# External_Camera_HAT_Regulators.net
KiCad netlist of a schematic drawn in Altium Designer
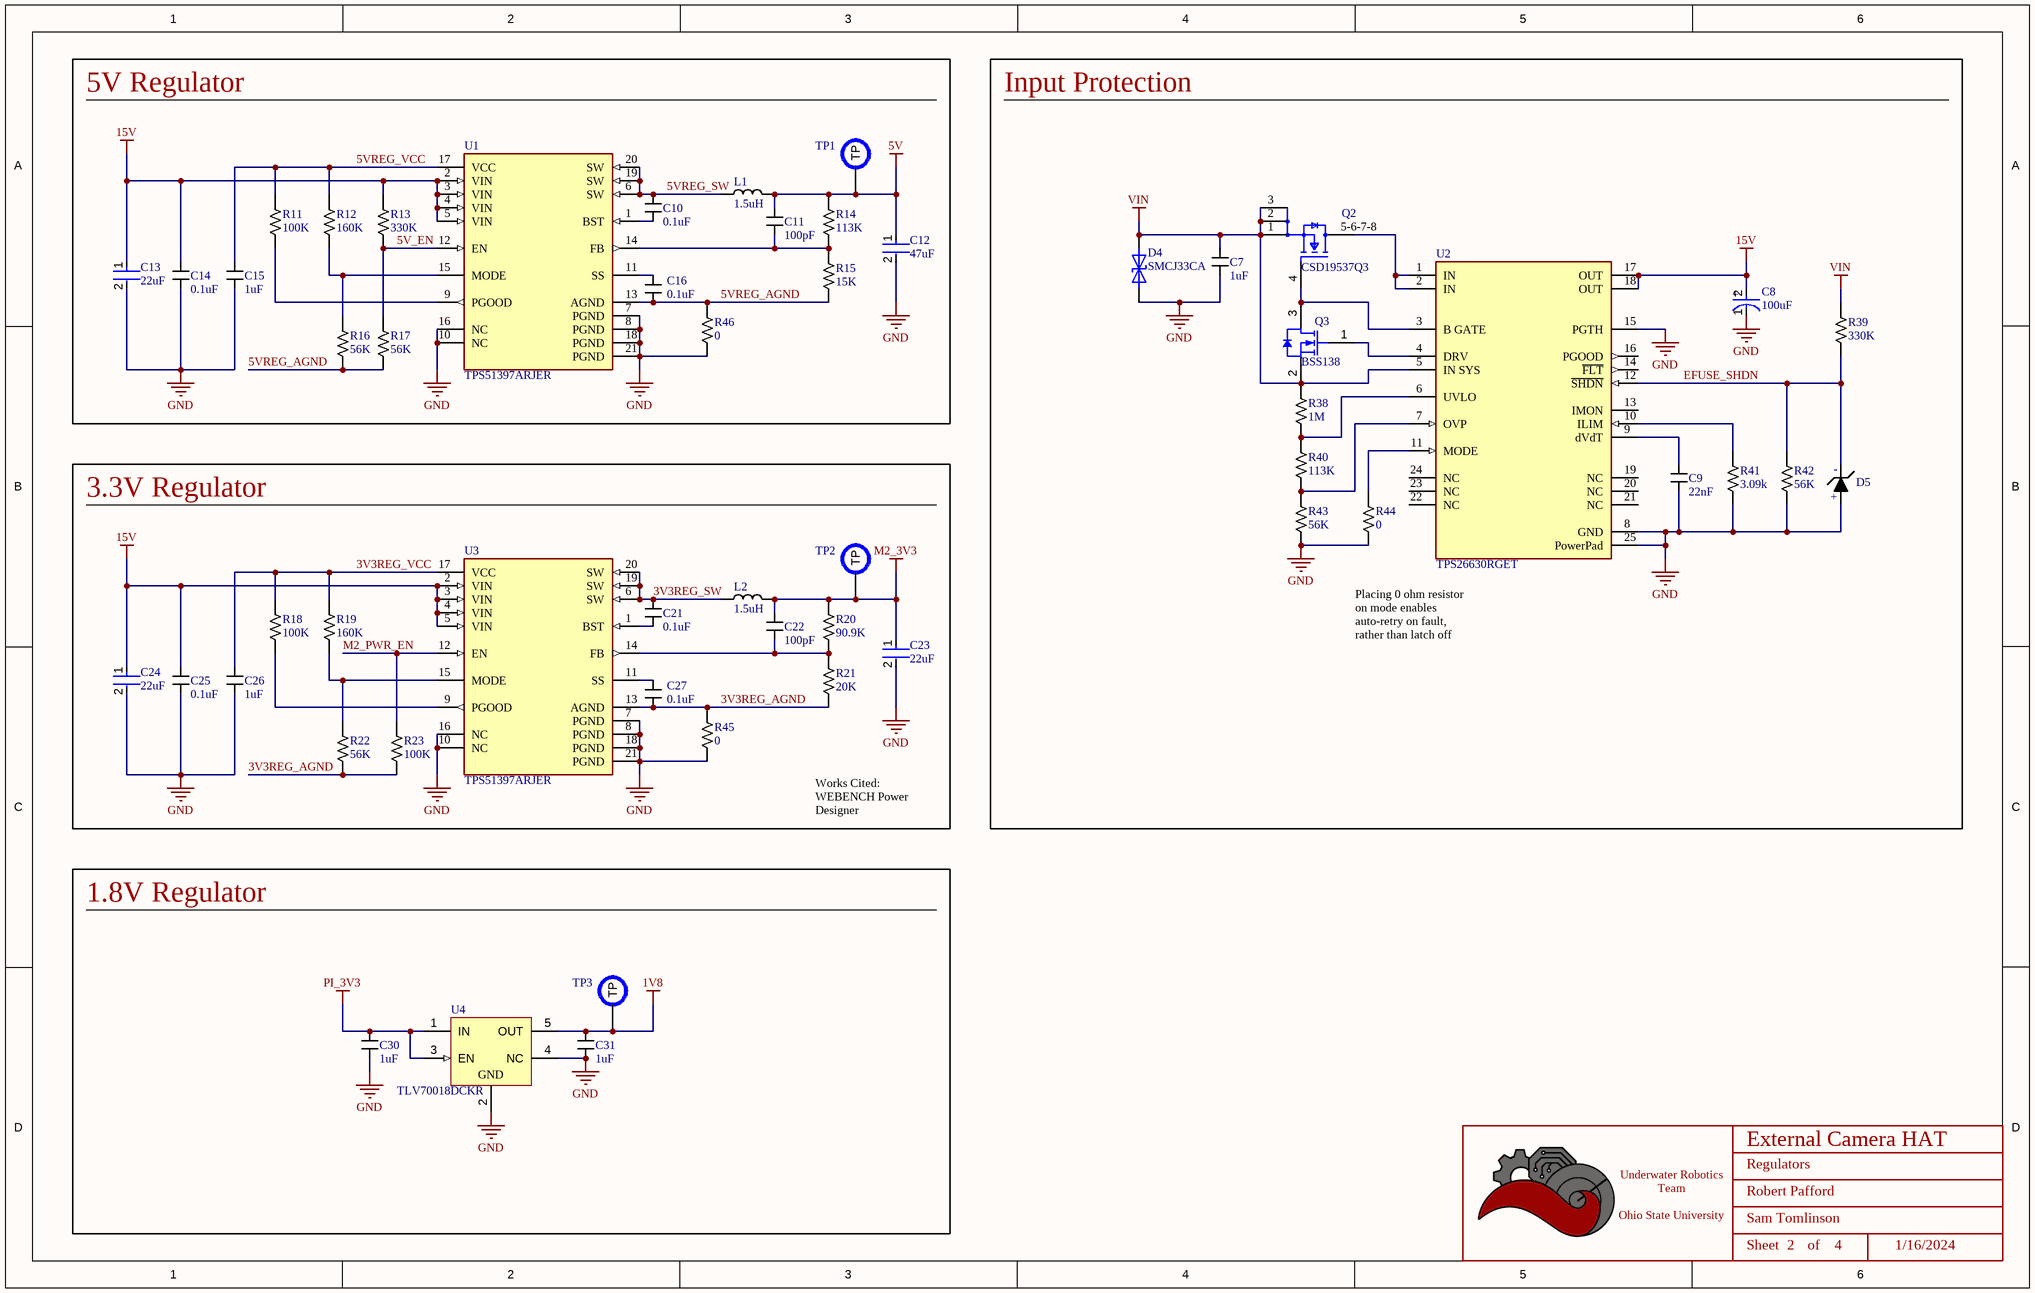
[diagram p0: External_Camera_HAT_Regulators.SchDoc]

(export (version "E")
  (design (tool "Eeschema 10.0.6"))
  (components
    (comp (ref "C7")
      (value "1uF")
      (footprint "CAPACITOR_0603")
      (description "Cap 1uF 25V +/-10%\r\nCeramic 0603")
      (fields
        (field (name "TOLERANCE") "+/- 10%")
        (field (name "VOLTAGE") "16V")
        (field (name "MADE BY") "Flip B")
      )
      (libsource (lib "Capacitors") (part "CAPACITOR_1uF_0603_25V"))
    )
    (comp (ref "C8")
      (value "100uF")
      (footprint "FP-UWT1H101MNL1GS-MFG")
      (description "CAP ALUM 100UF 20% 50V SMD")
      (fields (field (name "TOLERANCE") "20%") (field (name "VOLTAGE") "50V"))
      (libsource (lib "Altium Content Vault") (part "203bc49f2ac43e59fd269a8c329ed05"))
    )
    (comp (ref "C9")
      (value "22nF")
      (footprint "CAPACITOR_0402")
      (description "Cap 22nF 25V +/-10%\r\nCeramic 0402")
      (fields
        (field (name "TOLERANCE") "+/- 10%")
        (field (name "VOLTAGE") "25V")
        (field (name "MADE BY") "Robert Pafford")
      )
      (libsource (lib "Capacitors") (part "CAPACITOR_0.022uF_0402"))
    )
    (comp (ref "C10")
      (value "0.1uF")
      (footprint "CAPACITOR_0402")
      (description "Cap 100nF 25V +/-10%\r\nCeramic 0402")
      (fields
        (field (name "TOLERANCE") "+/- 10%")
        (field (name "VOLTAGE") "25V")
        (field (name "MADE BY") "Robert Pafford")
      )
      (libsource (lib "Capacitors") (part "CAPACITOR_0.1uF_0402"))
    )
    (comp (ref "C11")
      (value "100pF")
      (footprint "CAPACITOR_0402")
      (description "Cap 100pF 25V +/-10%\r\nCeramic 0402")
      (fields
        (field (name "TOLERANCE") "+/- 10%")
        (field (name "VOLTAGE") "25V")
        (field (name "MADE BY") "Robert Pafford")
      )
      (libsource (lib "Capacitors") (part "CAPACITOR_0.0001uF_0402"))
    )
    (comp (ref "C12")
      (value "GRM31CR61A476KE15L")
      (footprint "FP-GRM31C-0_2-e0_3_0_8-MFG")
      (description "Chip Multilayer Ceramic Capacitors for General Purpose, 1206, 47uF, X5R, 15%, 10%, 10V")
      (fields
        (field (name "TOLERANCE") "10%")
        (field (name "VOLTAGE") "10V")
        (field (name "CAPACITANCE") "47uF")
      )
      (libsource (lib "Altium Content Vault") (part "02cd4be3c70576c341d710602a673aa"))
    )
    (comp (ref "C13")
      (value "C2012X5R1V226M125AC")
      (footprint "FP-C2012-125-0_2-MFG")
      (description "Multilayer Ceramic Capacitors 22μF ±20% 35V X5R SMD 0805")
      (fields (field (name "TOLERANCE") "20%") (field (name "CAPACITANCE") "22uF"))
      (libsource (lib "Altium Content Vault") (part "b4654b650e69147ec39a6b967a45e02"))
    )
    (comp (ref "C14")
      (value "0.1uF")
      (footprint "CAPACITOR_0402")
      (description "Cap 100nF 25V +/-10%\r\nCeramic 0402")
      (fields
        (field (name "TOLERANCE") "+/- 10%")
        (field (name "VOLTAGE") "25V")
        (field (name "MADE BY") "Robert Pafford")
      )
      (libsource (lib "Capacitors") (part "CAPACITOR_0.1uF_0402"))
    )
    (comp (ref "C15")
      (value "1uF")
      (footprint "CAPACITOR_0402")
      (description "Cap 1uF 16V +/-10%\r\nCeramic 0402")
      (fields
        (field (name "TOLERANCE") "+/- 10%")
        (field (name "VOLTAGE") "16V")
        (field (name "MADE BY") "Robert Pafford")
      )
      (libsource (lib "Capacitors") (part "CAPACITOR_1uF_0402"))
    )
    (comp (ref "C16")
      (value "0.1uF")
      (footprint "CAPACITOR_0402")
      (description "Cap 100nF 25V +/-10%\r\nCeramic 0402")
      (fields
        (field (name "TOLERANCE") "+/- 10%")
        (field (name "VOLTAGE") "25V")
        (field (name "MADE BY") "Robert Pafford")
      )
      (libsource (lib "Capacitors") (part "CAPACITOR_0.1uF_0402"))
    )
    (comp (ref "C21")
      (value "0.1uF")
      (footprint "CAPACITOR_0402")
      (description "Cap 100nF 25V +/-10%\r\nCeramic 0402")
      (fields
        (field (name "TOLERANCE") "+/- 10%")
        (field (name "VOLTAGE") "25V")
        (field (name "MADE BY") "Robert Pafford")
      )
      (libsource (lib "Capacitors") (part "CAPACITOR_0.1uF_0402"))
    )
    (comp (ref "C22")
      (value "100pF")
      (footprint "CAPACITOR_0402")
      (description "Cap 100pF 25V +/-10%\r\nCeramic 0402")
      (fields
        (field (name "TOLERANCE") "+/- 10%")
        (field (name "VOLTAGE") "25V")
        (field (name "MADE BY") "Robert Pafford")
      )
      (libsource (lib "Capacitors") (part "CAPACITOR_0.0001uF_0402"))
    )
    (comp (ref "C23")
      (value "C2012X5R1V226M125AC")
      (footprint "FP-C2012-125-0_2-MFG")
      (description "Multilayer Ceramic Capacitors 22μF ±20% 35V X5R SMD 0805")
      (fields (field (name "TOLERANCE") "20%") (field (name "CAPACITANCE") "22uF"))
      (libsource (lib "Altium Content Vault") (part "b4654b650e69147ec39a6b967a45e02"))
    )
    (comp (ref "C24")
      (value "C2012X5R1V226M125AC")
      (footprint "FP-C2012-125-0_2-MFG")
      (description "Multilayer Ceramic Capacitors 22μF ±20% 35V X5R SMD 0805")
      (fields (field (name "TOLERANCE") "20%") (field (name "CAPACITANCE") "22uF"))
      (libsource (lib "Altium Content Vault") (part "b4654b650e69147ec39a6b967a45e02"))
    )
    (comp (ref "C25")
      (value "0.1uF")
      (footprint "CAPACITOR_0402")
      (description "Cap 100nF 25V +/-10%\r\nCeramic 0402")
      (fields
        (field (name "TOLERANCE") "+/- 10%")
        (field (name "VOLTAGE") "25V")
        (field (name "MADE BY") "Robert Pafford")
      )
      (libsource (lib "Capacitors") (part "CAPACITOR_0.1uF_0402"))
    )
    (comp (ref "C26")
      (value "1uF")
      (footprint "CAPACITOR_0402")
      (description "Cap 1uF 16V +/-10%\r\nCeramic 0402")
      (fields
        (field (name "TOLERANCE") "+/- 10%")
        (field (name "VOLTAGE") "16V")
        (field (name "MADE BY") "Robert Pafford")
      )
      (libsource (lib "Capacitors") (part "CAPACITOR_1uF_0402"))
    )
    (comp (ref "C27")
      (value "0.1uF")
      (footprint "CAPACITOR_0402")
      (description "Cap 100nF 25V +/-10%\r\nCeramic 0402")
      (fields
        (field (name "TOLERANCE") "+/- 10%")
        (field (name "VOLTAGE") "25V")
        (field (name "MADE BY") "Robert Pafford")
      )
      (libsource (lib "Capacitors") (part "CAPACITOR_0.1uF_0402"))
    )
    (comp (ref "C30")
      (value "1uF")
      (footprint "CAPACITOR_0402")
      (description "Cap 1uF 16V +/-10%\r\nCeramic 0402")
      (fields
        (field (name "TOLERANCE") "+/- 10%")
        (field (name "VOLTAGE") "16V")
        (field (name "MADE BY") "Robert Pafford")
      )
      (libsource (lib "Capacitors") (part "CAPACITOR_1uF_0402"))
    )
    (comp (ref "C31")
      (value "1uF")
      (footprint "CAPACITOR_0402")
      (description "Cap 1uF 16V +/-10%\r\nCeramic 0402")
      (fields
        (field (name "TOLERANCE") "+/- 10%")
        (field (name "VOLTAGE") "16V")
        (field (name "MADE BY") "Robert Pafford")
      )
      (libsource (lib "Capacitors") (part "CAPACITOR_1uF_0402"))
    )
    (comp (ref "D4")
      (value "SMCJ33CA")
      (footprint "DIOM7959X262N")
      (description "53.3V Clamp 28.1A Ipp Tvs Diode Surface Mount SMC (DO-214AB)")
      (fields (field (name "MF") "Bourns Inc."))
      (libsource (lib "Diodes") (part "SMCJ33CA"))
    )
    (comp (ref "D5")
      (value "Zener_Diode_3.3V_250mW_1")
      (footprint "SOD-123")
      (description "Zener Diode ¦ 3.3 V ¦ 250 mW ¦ SOT-23")
      (fields (field (name "POWER") "410mW") (field (name "MADE BY") "Nathan A"))
      (libsource (lib "Diodes") (part "Zener_Diode_3.3V_250mW_1"))
    )
    (comp (ref "L1")
      (value "1.5uH")
      (footprint "IHLP2525EZ")
      (description "Inductor Shielded 1.5uH 12A +/-20%")
      (fields
        (field (name "TOLERANCE") "+/- 20%")
        (field (name "Comment") "1.5uH Shielded")
        (field (name "MADE BY") "Robert Pafford")
      )
      (libsource (lib "Inductors") (part "INDUCTOR_1.5uH_IHLP2525EZ_1"))
    )
    (comp (ref "L2")
      (value "1.5uH")
      (footprint "IHLP2525EZ")
      (description "Inductor Shielded 1.5uH 12A +/-20%")
      (fields
        (field (name "TOLERANCE") "+/- 20%")
        (field (name "Comment") "1.5uH Shielded")
        (field (name "MADE BY") "Robert Pafford")
      )
      (libsource (lib "Inductors") (part "INDUCTOR_1.5uH_IHLP2525EZ_1"))
    )
    (comp (ref "Q2")
      (value "CSD19537Q3")
      (footprint "FP-DQG0008A-MFG")
      (description "MOSFET N-CH 100V 50A 8VSON")
      (libsource (lib "Altium Content Vault") (part "7382af88e928fdc71488234cfaaf11c"))
    )
    (comp (ref "Q3")
      (value "BSS138")
      (footprint "FAIR-SOT23-3_V")
      (fields (field (name "MANUFACTURER") "Fairchild") (field (name "POWER") "360mW"))
      (libsource (lib "Ohio State Capstone Team 20") (part "NEMOS-GSD-3"))
    )
    (comp (ref "R11")
      (value "100k Ohm 1% 1/16W")
      (footprint "RESISTOR_0402")
      (description "RES 100k OHM 1% 1/16W 0402")
      (fields
        (field (name "TOLERANCE") "+/- 1%")
        (field (name "VALUE  (OHMS)") "100K")
        (field (name "MADE BY") "Robert Pafford")
      )
      (libsource (lib "Resistors") (part "RESISTOR_100K_0402"))
    )
    (comp (ref "R12")
      (value "160k Ohm 1% 1/16W")
      (footprint "RESISTOR_0402")
      (description "RES 160k OHM 1% 1/16W 0402")
      (fields
        (field (name "TOLERANCE") "+/- 1%")
        (field (name "VALUE  (OHMS)") "160K")
        (field (name "MADE BY") "Robert Pafford")
      )
      (libsource (lib "Resistors") (part "RESISTOR_160K_0402"))
    )
    (comp (ref "R13")
      (value "330k Ohm 1% 1/16W")
      (footprint "RESISTOR_0402")
      (description "RES 330k OHM 1% 1/16W 0402")
      (fields
        (field (name "TOLERANCE") "+/- 1%")
        (field (name "VALUE  (OHMS)") "330K")
        (field (name "MADE BY") "Robert Pafford")
      )
      (libsource (lib "Resistors") (part "RESISTOR_330K_0402"))
    )
    (comp (ref "R14")
      (value "113k Ohm 1% 1/16W")
      (footprint "RESISTOR_0402")
      (description "RES 113k OHM 1% 1/16W 0402")
      (fields
        (field (name "TOLERANCE") "+/- 1%")
        (field (name "VALUE  (OHMS)") "113K")
        (field (name "MADE BY") "Robert Pafford")
      )
      (libsource (lib "Resistors") (part "RESISTOR_113K_0402"))
    )
    (comp (ref "R15")
      (value "15k Ohm 1% 1/16W")
      (footprint "RESISTOR_0402")
      (description "RES 15k OHM 1% 1/16W 0402")
      (fields
        (field (name "TOLERANCE") "+/- 1%")
        (field (name "VALUE  (OHMS)") "15K")
        (field (name "MADE BY") "Robert Pafford")
      )
      (libsource (lib "Resistors") (part "RESISTOR_15K_0402"))
    )
    (comp (ref "R16")
      (value "56k Ohm 1% 1/16W")
      (footprint "RESISTOR_0402")
      (description "RES 56k OHM 1% 1/16W 0402")
      (fields
        (field (name "TOLERANCE") "+/- 1%")
        (field (name "VALUE  (OHMS)") "56K")
        (field (name "MADE BY") "Robert Pafford")
      )
      (libsource (lib "Resistors") (part "RESISTOR_56K_0402"))
    )
    (comp (ref "R17")
      (value "56k Ohm 1% 1/16W")
      (footprint "RESISTOR_0402")
      (description "RES 56k OHM 1% 1/16W 0402")
      (fields
        (field (name "TOLERANCE") "+/- 1%")
        (field (name "VALUE  (OHMS)") "56K")
        (field (name "MADE BY") "Robert Pafford")
      )
      (libsource (lib "Resistors") (part "RESISTOR_56K_0402"))
    )
    (comp (ref "R18")
      (value "100k Ohm 1% 1/16W")
      (footprint "RESISTOR_0402")
      (description "RES 100k OHM 1% 1/16W 0402")
      (fields
        (field (name "TOLERANCE") "+/- 1%")
        (field (name "VALUE  (OHMS)") "100K")
        (field (name "MADE BY") "Robert Pafford")
      )
      (libsource (lib "Resistors") (part "RESISTOR_100K_0402"))
    )
    (comp (ref "R19")
      (value "160k Ohm 1% 1/16W")
      (footprint "RESISTOR_0402")
      (description "RES 160k OHM 1% 1/16W 0402")
      (fields
        (field (name "TOLERANCE") "+/- 1%")
        (field (name "VALUE  (OHMS)") "160K")
        (field (name "MADE BY") "Robert Pafford")
      )
      (libsource (lib "Resistors") (part "RESISTOR_160K_0402"))
    )
    (comp (ref "R20")
      (value "90.9k Ohm 1% 1/16W")
      (footprint "RESISTOR_0402")
      (description "RES 90.9k OHM 1% 1/16W 0402")
      (fields
        (field (name "TOLERANCE") "+/- 1%")
        (field (name "VALUE  (OHMS)") "90.9K")
        (field (name "MADE BY") "Robert Pafford")
      )
      (libsource (lib "Resistors") (part "RESISTOR_90.9K_0402"))
    )
    (comp (ref "R21")
      (value "20k Ohm 1% 1/16W")
      (footprint "RESISTOR_0402")
      (description "RES 20k OHM 1% 1/16W 0402")
      (fields
        (field (name "TOLERANCE") "+/- 1%")
        (field (name "VALUE  (OHMS)") "20K")
        (field (name "MADE BY") "Robert Pafford")
      )
      (libsource (lib "Resistors") (part "RESISTOR_20K_0402"))
    )
    (comp (ref "R22")
      (value "56k Ohm 1% 1/16W")
      (footprint "RESISTOR_0402")
      (description "RES 56k OHM 1% 1/16W 0402")
      (fields
        (field (name "TOLERANCE") "+/- 1%")
        (field (name "VALUE  (OHMS)") "56K")
        (field (name "MADE BY") "Robert Pafford")
      )
      (libsource (lib "Resistors") (part "RESISTOR_56K_0402"))
    )
    (comp (ref "R23")
      (value "100k Ohm 1% 1/16W")
      (footprint "RESISTOR_0402")
      (description "RES 100k OHM 1% 1/16W 0402")
      (fields
        (field (name "TOLERANCE") "+/- 1%")
        (field (name "VALUE  (OHMS)") "100K")
        (field (name "MADE BY") "Robert Pafford")
      )
      (libsource (lib "Resistors") (part "RESISTOR_100K_0402"))
    )
    (comp (ref "R38")
      (value "1M Ohm 1% 1/16W")
      (footprint "RESISTOR_0402")
      (description "RES 1M OHM 1% 1/16W 0402")
      (fields
        (field (name "TOLERANCE") "+/- 1%")
        (field (name "VALUE  (OHMS)") "1M")
        (field (name "MADE BY") "Robert Pafford")
      )
      (libsource (lib "Resistors") (part "RESISTOR_1M_0402"))
    )
    (comp (ref "R39")
      (value "330k Ohm 1% 1/16W")
      (footprint "RESISTOR_0402")
      (description "RES 330k OHM 1% 1/16W 0402")
      (fields
        (field (name "TOLERANCE") "+/- 1%")
        (field (name "VALUE  (OHMS)") "330K")
        (field (name "MADE BY") "Robert Pafford")
      )
      (libsource (lib "Resistors") (part "RESISTOR_330K_0402"))
    )
    (comp (ref "R40")
      (value "113k Ohm 1% 1/16W")
      (footprint "RESISTOR_0402")
      (description "RES 113k OHM 1% 1/16W 0402")
      (fields
        (field (name "TOLERANCE") "+/- 1%")
        (field (name "VALUE  (OHMS)") "113K")
        (field (name "MADE BY") "Robert Pafford")
      )
      (libsource (lib "Resistors") (part "RESISTOR_113K_0402"))
    )
    (comp (ref "R41")
      (value "3.09k Ohm 1% 1/16W")
      (footprint "RESISTOR_0402")
      (description "RES 3.09k OHM 1% 1/16W 0402")
      (fields
        (field (name "TOLERANCE") "+/- 1%")
        (field (name "VALUE  (OHMS)") "3.09k")
        (field (name "MADE BY") "Robert Pafford")
      )
      (libsource (lib "Resistors") (part "RESISTOR_3.09K_0402"))
    )
    (comp (ref "R42")
      (value "56k Ohm 1% 1/16W")
      (footprint "RESISTOR_0402")
      (description "RES 56k OHM 1% 1/16W 0402")
      (fields
        (field (name "TOLERANCE") "+/- 1%")
        (field (name "VALUE  (OHMS)") "56K")
        (field (name "MADE BY") "Robert Pafford")
      )
      (libsource (lib "Resistors") (part "RESISTOR_56K_0402"))
    )
    (comp (ref "R43")
      (value "56k Ohm 1% 1/16W")
      (footprint "RESISTOR_0402")
      (description "RES 56k OHM 1% 1/16W 0402")
      (fields
        (field (name "TOLERANCE") "+/- 1%")
        (field (name "VALUE  (OHMS)") "56K")
        (field (name "MADE BY") "Robert Pafford")
      )
      (libsource (lib "Resistors") (part "RESISTOR_56K_0402"))
    )
    (comp (ref "R44")
      (value "0 Ohm 1% 1/16W")
      (footprint "RESISTOR_0402")
      (description "RES 0 OHM 1% 1/16W 0402")
      (fields
        (field (name "TOLERANCE") "+/- 1%")
        (field (name "VALUE  (OHMS)") "0")
        (field (name "MADE BY") "Robert Pafford")
      )
      (libsource (lib "Resistors") (part "RESISTOR_0_0402"))
    )
    (comp (ref "R45")
      (value "0 Ohm 1% 1/16W")
      (footprint "RESISTOR_0402")
      (description "RES 0 OHM 1% 1/16W 0402")
      (fields
        (field (name "TOLERANCE") "+/- 1%")
        (field (name "VALUE  (OHMS)") "0")
        (field (name "MADE BY") "Robert Pafford")
      )
      (libsource (lib "Resistors") (part "RESISTOR_0_0402"))
    )
    (comp (ref "R46")
      (value "0 Ohm 1% 1/16W")
      (footprint "RESISTOR_0402")
      (description "RES 0 OHM 1% 1/16W 0402")
      (fields
        (field (name "TOLERANCE") "+/- 1%")
        (field (name "VALUE  (OHMS)") "0")
        (field (name "MADE BY") "Robert Pafford")
      )
      (libsource (lib "Resistors") (part "RESISTOR_0_0402"))
    )
    (comp (ref "TP1")
      (value "PCB Test Point")
      (footprint "TESTPOINT_1.2MM")
      (fields (field (name "MADE BY") "Robert Pafford"))
      (libsource (lib "Connectors") (part "TESTPOINT"))
    )
    (comp (ref "TP2")
      (value "PCB Test Point")
      (footprint "TESTPOINT_1.2MM")
      (fields (field (name "MADE BY") "Robert Pafford"))
      (libsource (lib "Connectors") (part "TESTPOINT"))
    )
    (comp (ref "TP3")
      (value "PCB Test Point")
      (footprint "TESTPOINT_1.2MM")
      (fields (field (name "MADE BY") "Robert Pafford"))
      (libsource (lib "Connectors") (part "TESTPOINT"))
    )
    (comp (ref "U1")
      (value "TPS51397ARJER")
      (footprint "FP-RJE0020B-MFG")
      (description "10-A SYNCHRONOUS STEP-DOWN REGUL")
      (libsource (lib "Altium Content Vault") (part "ab47a50a5143bf718f7c4e945efebe0"))
    )
    (comp (ref "U2")
      (value "TPS26630RGET")
      (footprint "FP-RGE0024H-MFG")
      (description "POWER MANAGEMENT")
      (libsource (lib "Altium Content Vault") (part "92e6325a0b2cd7354d0d77963e83935"))
    )
    (comp (ref "U3")
      (value "TPS51397ARJER")
      (footprint "FP-RJE0020B-MFG")
      (description "10-A SYNCHRONOUS STEP-DOWN REGUL")
      (libsource (lib "Altium Content Vault") (part "ab47a50a5143bf718f7c4e945efebe0"))
    )
    (comp (ref "U4")
      (value "TLV70018DCKR")
      (footprint "DCK0005A_N")
      (fields (field (name "MANUFACTURER") "Texas Instruments"))
      (libsource (lib "Altium Content Vault") (part "TI-TXX7XXXX-5"))
    )
  )
  (nets
    (net (code "1") (name "/3V3REG_AGND") (class "Default")
      (node (ref "C27") (pin "2") (pinfunction "2_2") (pintype "passive"))
      (node (ref "R21") (pin "2") (pinfunction "2_2") (pintype "passive"))
      (node (ref "R22") (pin "2") (pinfunction "2_2") (pintype "passive"))
      (node (ref "R23") (pin "2") (pinfunction "2_2") (pintype "passive"))
      (node (ref "R45") (pin "1") (pinfunction "1_1") (pintype "passive"))
      (node (ref "U3") (pin "13") (pinfunction "AGND_13") (pintype "power_in"))
    )
    (net (code "2") (name "/3V3REG_SW") (class "Default")
      (node (ref "C21") (pin "1") (pinfunction "1_1") (pintype "passive"))
      (node (ref "L2") (pin "2") (pinfunction "2_2") (pintype "passive"))
      (node (ref "U3") (pin "19") (pinfunction "SW_19") (pintype "input"))
      (node (ref "U3") (pin "20") (pinfunction "SW_20") (pintype "input"))
      (node (ref "U3") (pin "6") (pinfunction "SW_6") (pintype "input"))
    )
    (net (code "3") (name "/3V3REG_VCC") (class "Default")
      (node (ref "C26") (pin "1") (pinfunction "1_1") (pintype "passive"))
      (node (ref "R18") (pin "1") (pinfunction "1_1") (pintype "passive"))
      (node (ref "R19") (pin "1") (pinfunction "1_1") (pintype "passive"))
      (node (ref "U3") (pin "17") (pinfunction "VCC_17") (pintype "power_in"))
    )
    (net (code "4") (name "/5VREG_AGND") (class "Default")
      (node (ref "C16") (pin "2") (pinfunction "2_2") (pintype "passive"))
      (node (ref "R15") (pin "2") (pinfunction "2_2") (pintype "passive"))
      (node (ref "R16") (pin "2") (pinfunction "2_2") (pintype "passive"))
      (node (ref "R17") (pin "2") (pinfunction "2_2") (pintype "passive"))
      (node (ref "R46") (pin "1") (pinfunction "1_1") (pintype "passive"))
      (node (ref "U1") (pin "13") (pinfunction "AGND_13") (pintype "power_in"))
    )
    (net (code "5") (name "/5VREG_SW") (class "Default")
      (node (ref "C10") (pin "1") (pinfunction "1_1") (pintype "passive"))
      (node (ref "L1") (pin "2") (pinfunction "2_2") (pintype "passive"))
      (node (ref "U1") (pin "19") (pinfunction "SW_19") (pintype "input"))
      (node (ref "U1") (pin "20") (pinfunction "SW_20") (pintype "input"))
      (node (ref "U1") (pin "6") (pinfunction "SW_6") (pintype "input"))
    )
    (net (code "6") (name "/5VREG_VCC") (class "Default")
      (node (ref "C15") (pin "1") (pinfunction "1_1") (pintype "passive"))
      (node (ref "R11") (pin "1") (pinfunction "1_1") (pintype "passive"))
      (node (ref "R12") (pin "1") (pinfunction "1_1") (pintype "passive"))
      (node (ref "U1") (pin "17") (pinfunction "VCC_17") (pintype "power_in"))
    )
    (net (code "7") (name "/5V_EN") (class "Default")
      (node (ref "R13") (pin "2") (pinfunction "2_2") (pintype "passive"))
      (node (ref "R17") (pin "1") (pinfunction "1_1") (pintype "passive"))
      (node (ref "U1") (pin "12") (pinfunction "EN_12") (pintype "input"))
    )
    (net (code "8") (name "/EFUSE_SHDN") (class "Default")
      (node (ref "D5") (pin "2") (pinfunction "2_2") (pintype "passive"))
      (node (ref "R39") (pin "2") (pinfunction "2_2") (pintype "passive"))
      (node (ref "R42") (pin "1") (pinfunction "1_1") (pintype "passive"))
      (node (ref "U2") (pin "12") (pinfunction "~{SHDN}_12") (pintype "input"))
    )
    (net (code "9") (name "/M2_PWR_EN") (class "Default")
      (node (ref "R23") (pin "1") (pinfunction "1_1") (pintype "passive"))
      (node (ref "U3") (pin "12") (pinfunction "EN_12") (pintype "input"))
    )
    (net (code "10") (name "1V8") (class "Default")
      (node (ref "C31") (pin "1") (pinfunction "1_1") (pintype "passive"))
      (node (ref "TP3") (pin "TP") (pinfunction "TP_TP") (pintype "passive"))
      (node (ref "U4") (pin "5") (pinfunction "OUT_5") (pintype "power_in"))
    )
    (net (code "11") (name "5V") (class "Default")
      (node (ref "C11") (pin "1") (pinfunction "1_1") (pintype "passive"))
      (node (ref "C12") (pin "1") (pinfunction "1_1") (pintype "passive"))
      (node (ref "L1") (pin "1") (pinfunction "1_1") (pintype "passive"))
      (node (ref "R14") (pin "1") (pinfunction "1_1") (pintype "passive"))
      (node (ref "TP1") (pin "TP") (pinfunction "TP_TP") (pintype "passive"))
    )
    (net (code "12") (name "15V") (class "Default")
      (node (ref "C13") (pin "1") (pinfunction "1_1") (pintype "passive"))
      (node (ref "C14") (pin "1") (pinfunction "1_1") (pintype "passive"))
      (node (ref "C24") (pin "1") (pinfunction "1_1") (pintype "passive"))
      (node (ref "C25") (pin "1") (pinfunction "1_1") (pintype "passive"))
      (node (ref "C8") (pin "2") (pinfunction "A_2") (pintype "passive"))
      (node (ref "R13") (pin "1") (pinfunction "1_1") (pintype "passive"))
      (node (ref "U1") (pin "2") (pinfunction "VIN_2") (pintype "input"))
      (node (ref "U1") (pin "3") (pinfunction "VIN_3") (pintype "input"))
      (node (ref "U1") (pin "4") (pinfunction "VIN_4") (pintype "input"))
      (node (ref "U1") (pin "5") (pinfunction "VIN_5") (pintype "input"))
      (node (ref "U2") (pin "17") (pinfunction "OUT_17") (pintype "power_in"))
      (node (ref "U2") (pin "18") (pinfunction "OUT_18") (pintype "power_in"))
      (node (ref "U3") (pin "2") (pinfunction "VIN_2") (pintype "input"))
      (node (ref "U3") (pin "3") (pinfunction "VIN_3") (pintype "input"))
      (node (ref "U3") (pin "4") (pinfunction "VIN_4") (pintype "input"))
      (node (ref "U3") (pin "5") (pinfunction "VIN_5") (pintype "input"))
    )
    (net (code "13") (name "GND") (class "Default")
      (node (ref "C12") (pin "2") (pinfunction "2_2") (pintype "passive"))
      (node (ref "C13") (pin "2") (pinfunction "2_2") (pintype "passive"))
      (node (ref "C14") (pin "2") (pinfunction "2_2") (pintype "passive"))
      (node (ref "C15") (pin "2") (pinfunction "2_2") (pintype "passive"))
      (node (ref "C23") (pin "2") (pinfunction "2_2") (pintype "passive"))
      (node (ref "C24") (pin "2") (pinfunction "2_2") (pintype "passive"))
      (node (ref "C25") (pin "2") (pinfunction "2_2") (pintype "passive"))
      (node (ref "C26") (pin "2") (pinfunction "2_2") (pintype "passive"))
      (node (ref "C30") (pin "2") (pinfunction "2_2") (pintype "passive"))
      (node (ref "C31") (pin "2") (pinfunction "2_2") (pintype "passive"))
      (node (ref "C7") (pin "2") (pinfunction "2_2") (pintype "passive"))
      (node (ref "C8") (pin "1") (pinfunction "C_1") (pintype "passive"))
      (node (ref "C9") (pin "2") (pinfunction "2_2") (pintype "passive"))
      (node (ref "D4") (pin "1") (pinfunction "1_1") (pintype "passive"))
      (node (ref "D5") (pin "1") (pinfunction "1_1") (pintype "passive"))
      (node (ref "R41") (pin "2") (pinfunction "2_2") (pintype "passive"))
      (node (ref "R42") (pin "2") (pinfunction "2_2") (pintype "passive"))
      (node (ref "R43") (pin "2") (pinfunction "2_2") (pintype "passive"))
      (node (ref "R44") (pin "2") (pinfunction "2_2") (pintype "passive"))
      (node (ref "R45") (pin "2") (pinfunction "2_2") (pintype "passive"))
      (node (ref "R46") (pin "2") (pinfunction "2_2") (pintype "passive"))
      (node (ref "U1") (pin "10") (pinfunction "NC_10") (pintype "passive"))
      (node (ref "U1") (pin "16") (pinfunction "NC_16") (pintype "passive"))
      (node (ref "U1") (pin "18") (pinfunction "PGND_18") (pintype "power_in"))
      (node (ref "U1") (pin "21") (pinfunction "PGND_21") (pintype "power_in"))
      (node (ref "U1") (pin "7") (pinfunction "PGND_7") (pintype "power_in"))
      (node (ref "U1") (pin "8") (pinfunction "PGND_8") (pintype "power_in"))
      (node (ref "U2") (pin "15") (pinfunction "PGTH_15") (pintype "passive"))
      (node (ref "U2") (pin "25") (pinfunction "PowerPad_25") (pintype "power_in"))
      (node (ref "U2") (pin "8") (pinfunction "GND_8") (pintype "power_in"))
      (node (ref "U3") (pin "10") (pinfunction "NC_10") (pintype "passive"))
      (node (ref "U3") (pin "16") (pinfunction "NC_16") (pintype "passive"))
      (node (ref "U3") (pin "18") (pinfunction "PGND_18") (pintype "power_in"))
      (node (ref "U3") (pin "21") (pinfunction "PGND_21") (pintype "power_in"))
      (node (ref "U3") (pin "7") (pinfunction "PGND_7") (pintype "power_in"))
      (node (ref "U3") (pin "8") (pinfunction "PGND_8") (pintype "power_in"))
      (node (ref "U4") (pin "2") (pinfunction "GND_2") (pintype "power_in"))
      (node (ref "U4") (pin "4") (pinfunction "NC_4") (pintype "passive"))
    )
    (net (code "14") (name "M2_3V3") (class "Default")
      (node (ref "C22") (pin "1") (pinfunction "1_1") (pintype "passive"))
      (node (ref "C23") (pin "1") (pinfunction "1_1") (pintype "passive"))
      (node (ref "L2") (pin "1") (pinfunction "1_1") (pintype "passive"))
      (node (ref "R20") (pin "1") (pinfunction "1_1") (pintype "passive"))
      (node (ref "TP2") (pin "TP") (pinfunction "TP_TP") (pintype "passive"))
    )
    (net (code "15") (name "Net-(Q2-D)") (class "Default")
      (node (ref "Q2") (pin "5-6-7-8") (pinfunction "D_5-6-7-8") (pintype "passive"))
      (node (ref "U2") (pin "1") (pinfunction "IN_1") (pintype "power_in"))
      (node (ref "U2") (pin "2") (pinfunction "IN_2") (pintype "power_in"))
    )
    (net (code "16") (name "Net-(Q2-G)") (class "Default")
      (node (ref "Q2") (pin "4") (pinfunction "G_4") (pintype "passive"))
      (node (ref "Q3") (pin "3") (pinfunction "D_3") (pintype "passive"))
      (node (ref "U2") (pin "3") (pinfunction "B_GATE_3") (pintype "passive"))
    )
    (net (code "17") (name "Net-(Q3-G)") (class "Default")
      (node (ref "Q3") (pin "1") (pinfunction "G_1") (pintype "passive"))
      (node (ref "U2") (pin "4") (pinfunction "DRV_4") (pintype "passive"))
    )
    (net (code "18") (name "Net-(U1-BST)") (class "Default")
      (node (ref "C10") (pin "2") (pinfunction "2_2") (pintype "passive"))
      (node (ref "U1") (pin "1") (pinfunction "BST_1") (pintype "input"))
    )
    (net (code "19") (name "Net-(U1-FB)") (class "Default")
      (node (ref "C11") (pin "2") (pinfunction "2_2") (pintype "passive"))
      (node (ref "R14") (pin "2") (pinfunction "2_2") (pintype "passive"))
      (node (ref "R15") (pin "1") (pinfunction "1_1") (pintype "passive"))
      (node (ref "U1") (pin "14") (pinfunction "FB_14") (pintype "output"))
    )
    (net (code "20") (name "Net-(U1-MODE)") (class "Default")
      (node (ref "R12") (pin "2") (pinfunction "2_2") (pintype "passive"))
      (node (ref "R16") (pin "1") (pinfunction "1_1") (pintype "passive"))
      (node (ref "U1") (pin "15") (pinfunction "MODE_15") (pintype "passive"))
    )
    (net (code "21") (name "Net-(U1-PGOOD)") (class "Default")
      (node (ref "R11") (pin "2") (pinfunction "2_2") (pintype "passive"))
      (node (ref "U1") (pin "9") (pinfunction "PGOOD_9") (pintype "output"))
    )
    (net (code "22") (name "Net-(U1-SS)") (class "Default")
      (node (ref "C16") (pin "1") (pinfunction "1_1") (pintype "passive"))
      (node (ref "U1") (pin "11") (pinfunction "SS_11") (pintype "passive"))
    )
    (net (code "23") (name "Net-(U2-ILIM)") (class "Default")
      (node (ref "R41") (pin "1") (pinfunction "1_1") (pintype "passive"))
      (node (ref "U2") (pin "10") (pinfunction "ILIM_10") (pintype "input"))
    )
    (net (code "24") (name "Net-(U2-MODE)") (class "Default")
      (node (ref "R44") (pin "1") (pinfunction "1_1") (pintype "passive"))
      (node (ref "U2") (pin "11") (pinfunction "MODE_11") (pintype "input"))
    )
    (net (code "25") (name "Net-(U2-OVP)") (class "Default")
      (node (ref "R40") (pin "2") (pinfunction "2_2") (pintype "passive"))
      (node (ref "R43") (pin "1") (pinfunction "1_1") (pintype "passive"))
      (node (ref "U2") (pin "7") (pinfunction "OVP_7") (pintype "input"))
    )
    (net (code "26") (name "Net-(U2-UVLO)") (class "Default")
      (node (ref "R38") (pin "2") (pinfunction "2_2") (pintype "passive"))
      (node (ref "R40") (pin "1") (pinfunction "1_1") (pintype "passive"))
      (node (ref "U2") (pin "6") (pinfunction "UVLO_6") (pintype "passive"))
    )
    (net (code "27") (name "Net-(U2-dVdT)") (class "Default")
      (node (ref "C9") (pin "1") (pinfunction "1_1") (pintype "passive"))
      (node (ref "U2") (pin "9") (pinfunction "dVdT_9") (pintype "passive"))
    )
    (net (code "28") (name "Net-(U3-BST)") (class "Default")
      (node (ref "C21") (pin "2") (pinfunction "2_2") (pintype "passive"))
      (node (ref "U3") (pin "1") (pinfunction "BST_1") (pintype "input"))
    )
    (net (code "29") (name "Net-(U3-FB)") (class "Default")
      (node (ref "C22") (pin "2") (pinfunction "2_2") (pintype "passive"))
      (node (ref "R20") (pin "2") (pinfunction "2_2") (pintype "passive"))
      (node (ref "R21") (pin "1") (pinfunction "1_1") (pintype "passive"))
      (node (ref "U3") (pin "14") (pinfunction "FB_14") (pintype "output"))
    )
    (net (code "30") (name "Net-(U3-MODE)") (class "Default")
      (node (ref "R19") (pin "2") (pinfunction "2_2") (pintype "passive"))
      (node (ref "R22") (pin "1") (pinfunction "1_1") (pintype "passive"))
      (node (ref "U3") (pin "15") (pinfunction "MODE_15") (pintype "passive"))
    )
    (net (code "31") (name "Net-(U3-PGOOD)") (class "Default")
      (node (ref "R18") (pin "2") (pinfunction "2_2") (pintype "passive"))
      (node (ref "U3") (pin "9") (pinfunction "PGOOD_9") (pintype "output"))
    )
    (net (code "32") (name "Net-(U3-SS)") (class "Default")
      (node (ref "C27") (pin "1") (pinfunction "1_1") (pintype "passive"))
      (node (ref "U3") (pin "11") (pinfunction "SS_11") (pintype "passive"))
    )
    (net (code "33") (name "PI_3V3") (class "Default")
      (node (ref "C30") (pin "1") (pinfunction "1_1") (pintype "passive"))
      (node (ref "U4") (pin "1") (pinfunction "IN_1") (pintype "power_in"))
      (node (ref "U4") (pin "3") (pinfunction "EN_3") (pintype "input"))
    )
    (net (code "34") (name "VIN") (class "Default")
      (node (ref "C7") (pin "1") (pinfunction "1_1") (pintype "passive"))
      (node (ref "D4") (pin "2") (pinfunction "2_2") (pintype "passive"))
      (node (ref "Q2") (pin "1") (pinfunction "S_1") (pintype "passive"))
      (node (ref "Q2") (pin "2") (pinfunction "S_2") (pintype "passive"))
      (node (ref "Q2") (pin "3") (pinfunction "S_3") (pintype "passive"))
      (node (ref "Q3") (pin "2") (pinfunction "S_2") (pintype "passive"))
      (node (ref "R38") (pin "1") (pinfunction "1_1") (pintype "passive"))
      (node (ref "R39") (pin "1") (pinfunction "1_1") (pintype "passive"))
      (node (ref "U2") (pin "5") (pinfunction "IN_SYS_5") (pintype "power_in"))
    )
    (net (code "35") (name "unconnected-(U2-IMON-Pad13)") (class "Default")
      (node (ref "U2") (pin "13") (pinfunction "IMON_13") (pintype "passive"))
    )
    (net (code "36") (name "unconnected-(U2-NC-Pad19)") (class "Default")
      (node (ref "U2") (pin "19") (pinfunction "NC_19") (pintype "passive"))
    )
    (net (code "37") (name "unconnected-(U2-NC-Pad20)") (class "Default")
      (node (ref "U2") (pin "20") (pinfunction "NC_20") (pintype "passive"))
    )
    (net (code "38") (name "unconnected-(U2-NC-Pad21)") (class "Default")
      (node (ref "U2") (pin "21") (pinfunction "NC_21") (pintype "passive"))
    )
    (net (code "39") (name "unconnected-(U2-NC-Pad22)") (class "Default")
      (node (ref "U2") (pin "22") (pinfunction "NC_22") (pintype "passive"))
    )
    (net (code "40") (name "unconnected-(U2-NC-Pad23)") (class "Default")
      (node (ref "U2") (pin "23") (pinfunction "NC_23") (pintype "passive"))
    )
    (net (code "41") (name "unconnected-(U2-NC-Pad24)") (class "Default")
      (node (ref "U2") (pin "24") (pinfunction "NC_24") (pintype "passive"))
    )
    (net (code "42") (name "unconnected-(U2-PGOOD-Pad16)") (class "Default")
      (node (ref "U2") (pin "16") (pinfunction "PGOOD_16") (pintype "output"))
    )
    (net (code "43") (name "unconnected-(U2-~{FLT}-Pad14)") (class "Default")
      (node (ref "U2") (pin "14") (pinfunction "~{FLT}_14") (pintype "output"))
    )
  )
)
